# hybrid.net
KiCad netlist of a schematic drawn in EAGLE
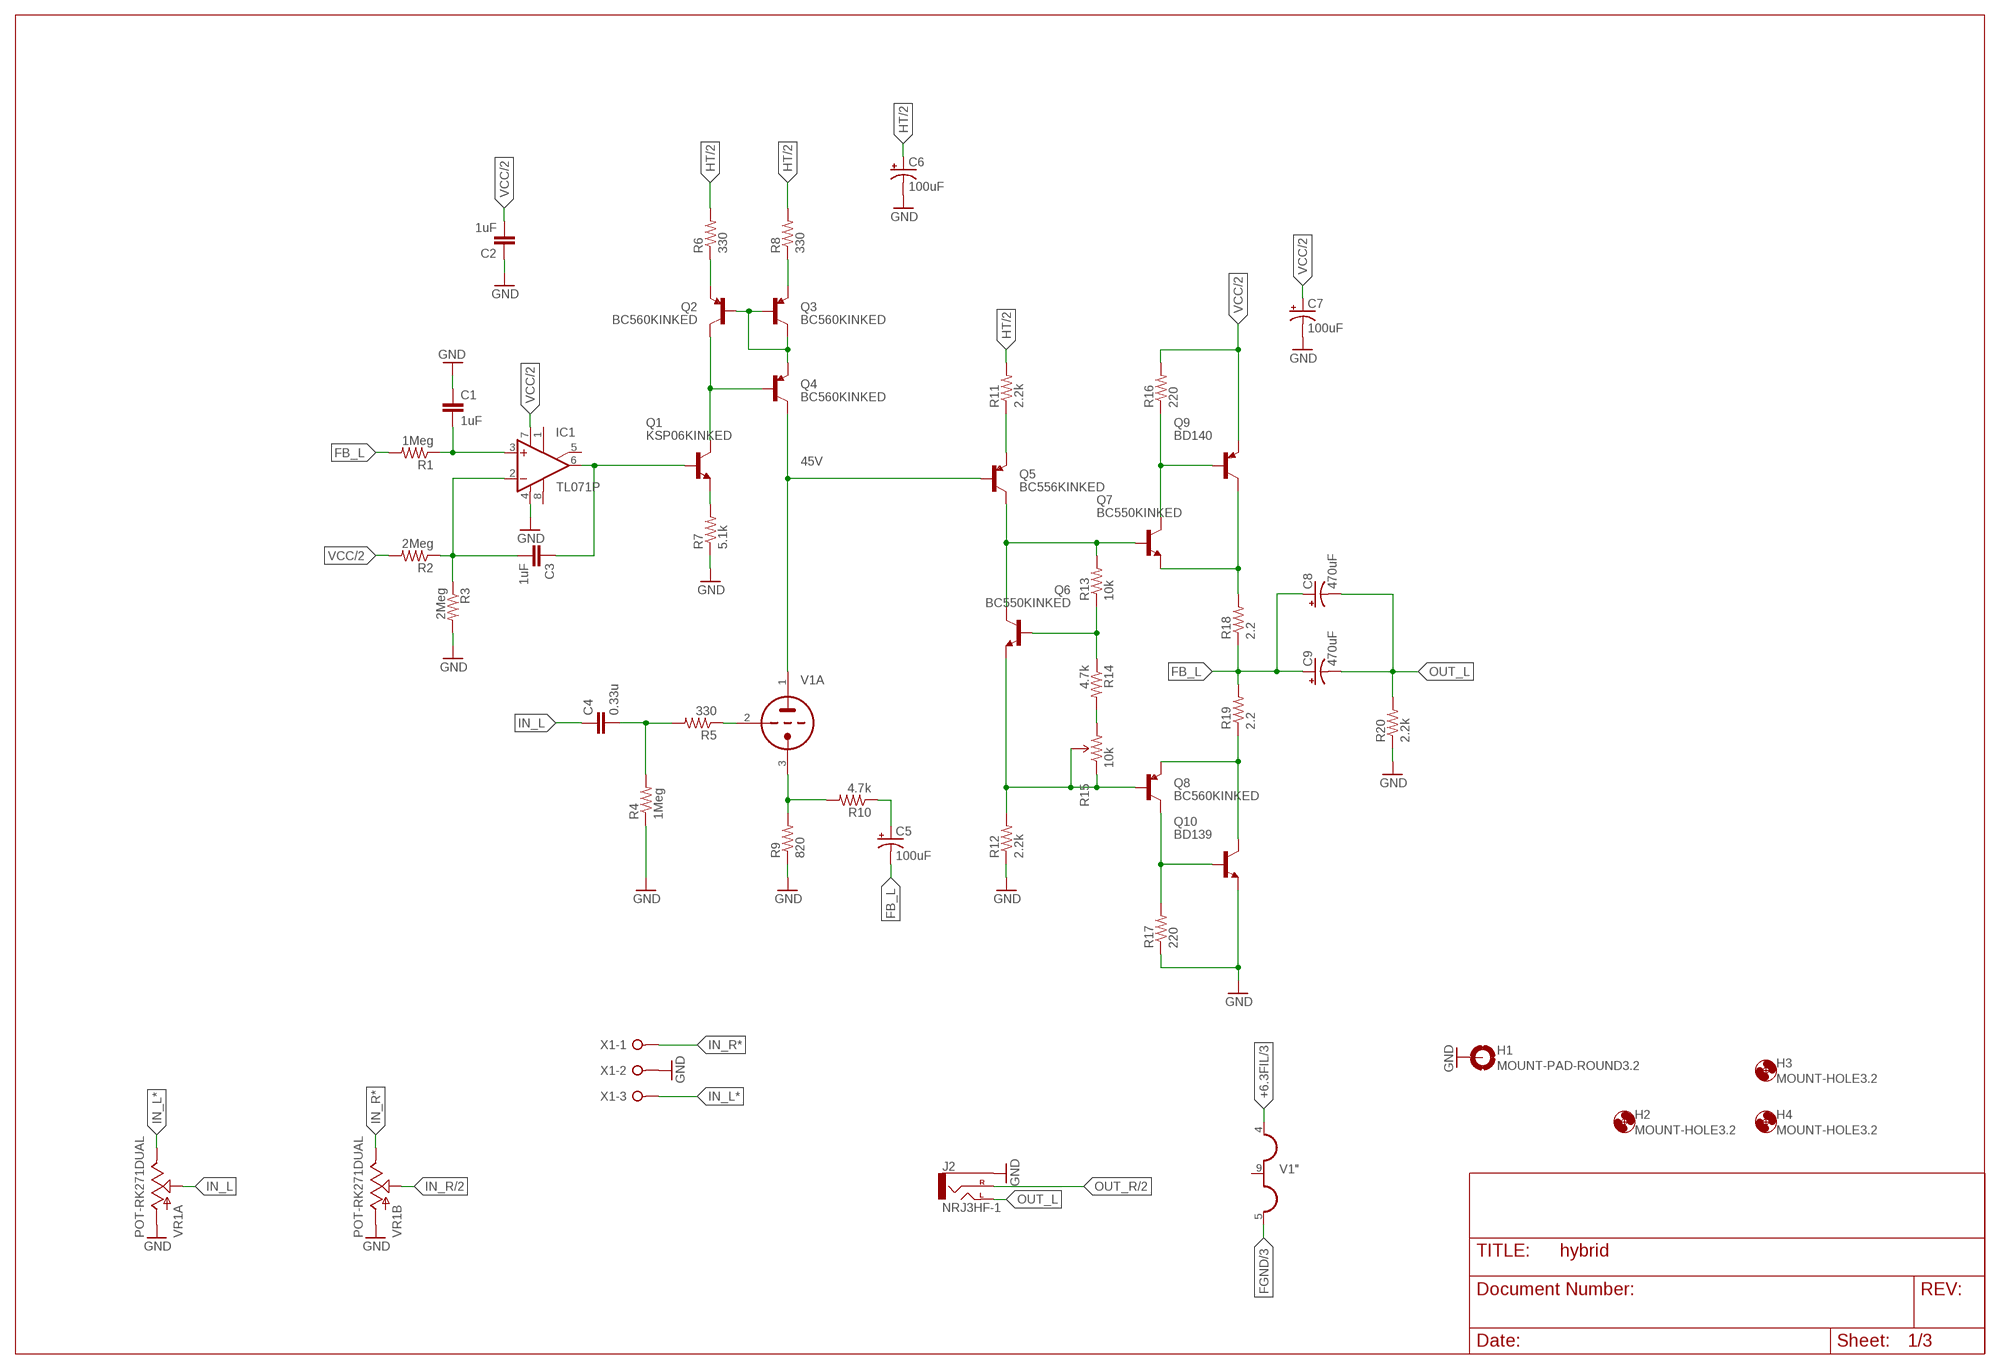
[diagram p0: schematic, sheet 1]
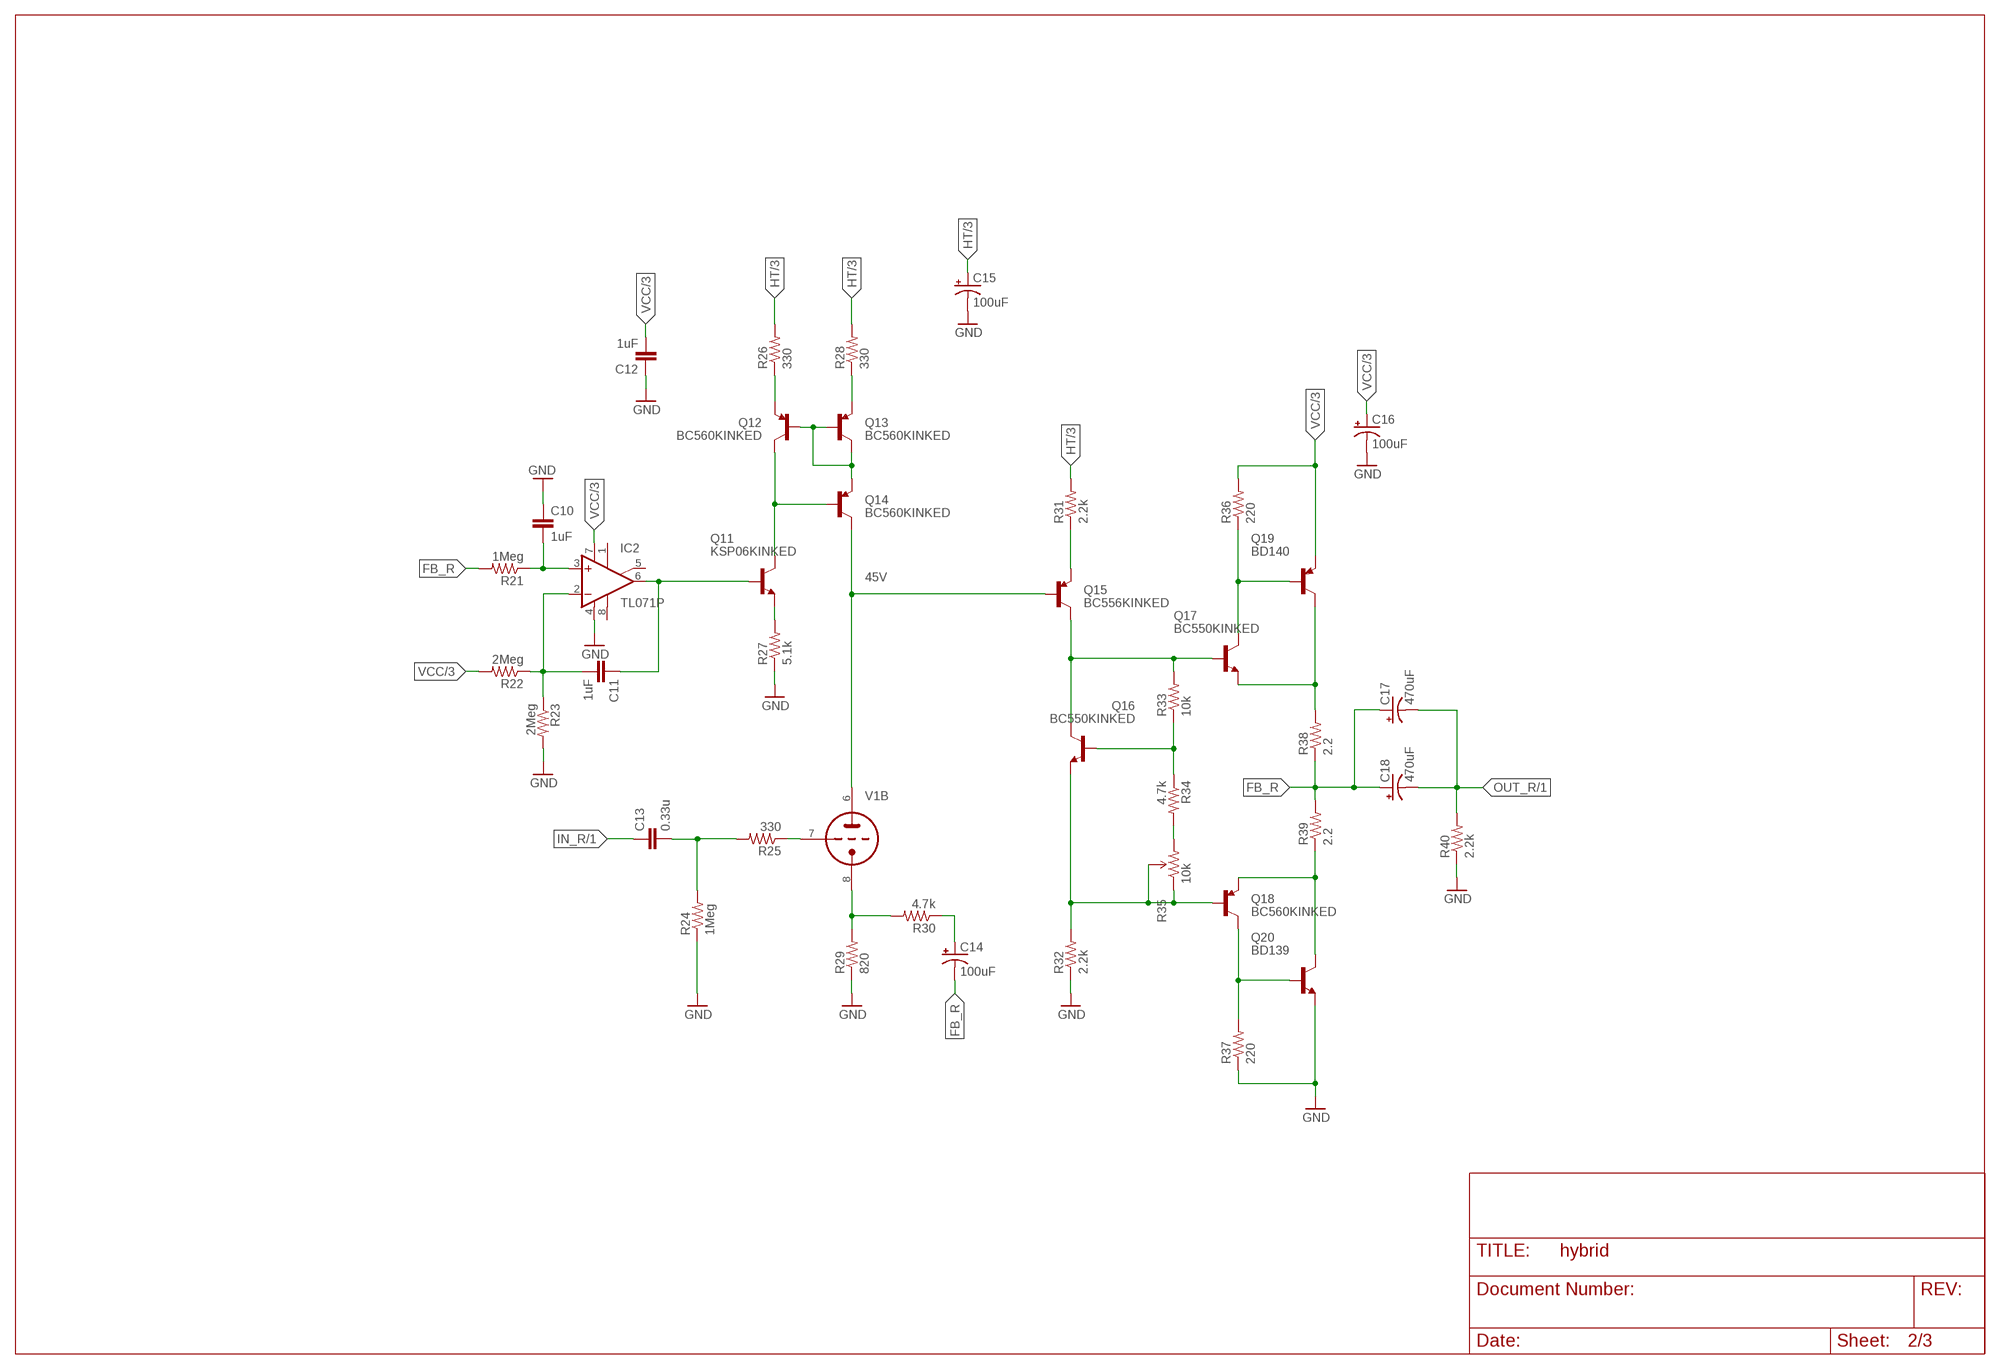
[diagram p1: schematic, sheet 2]
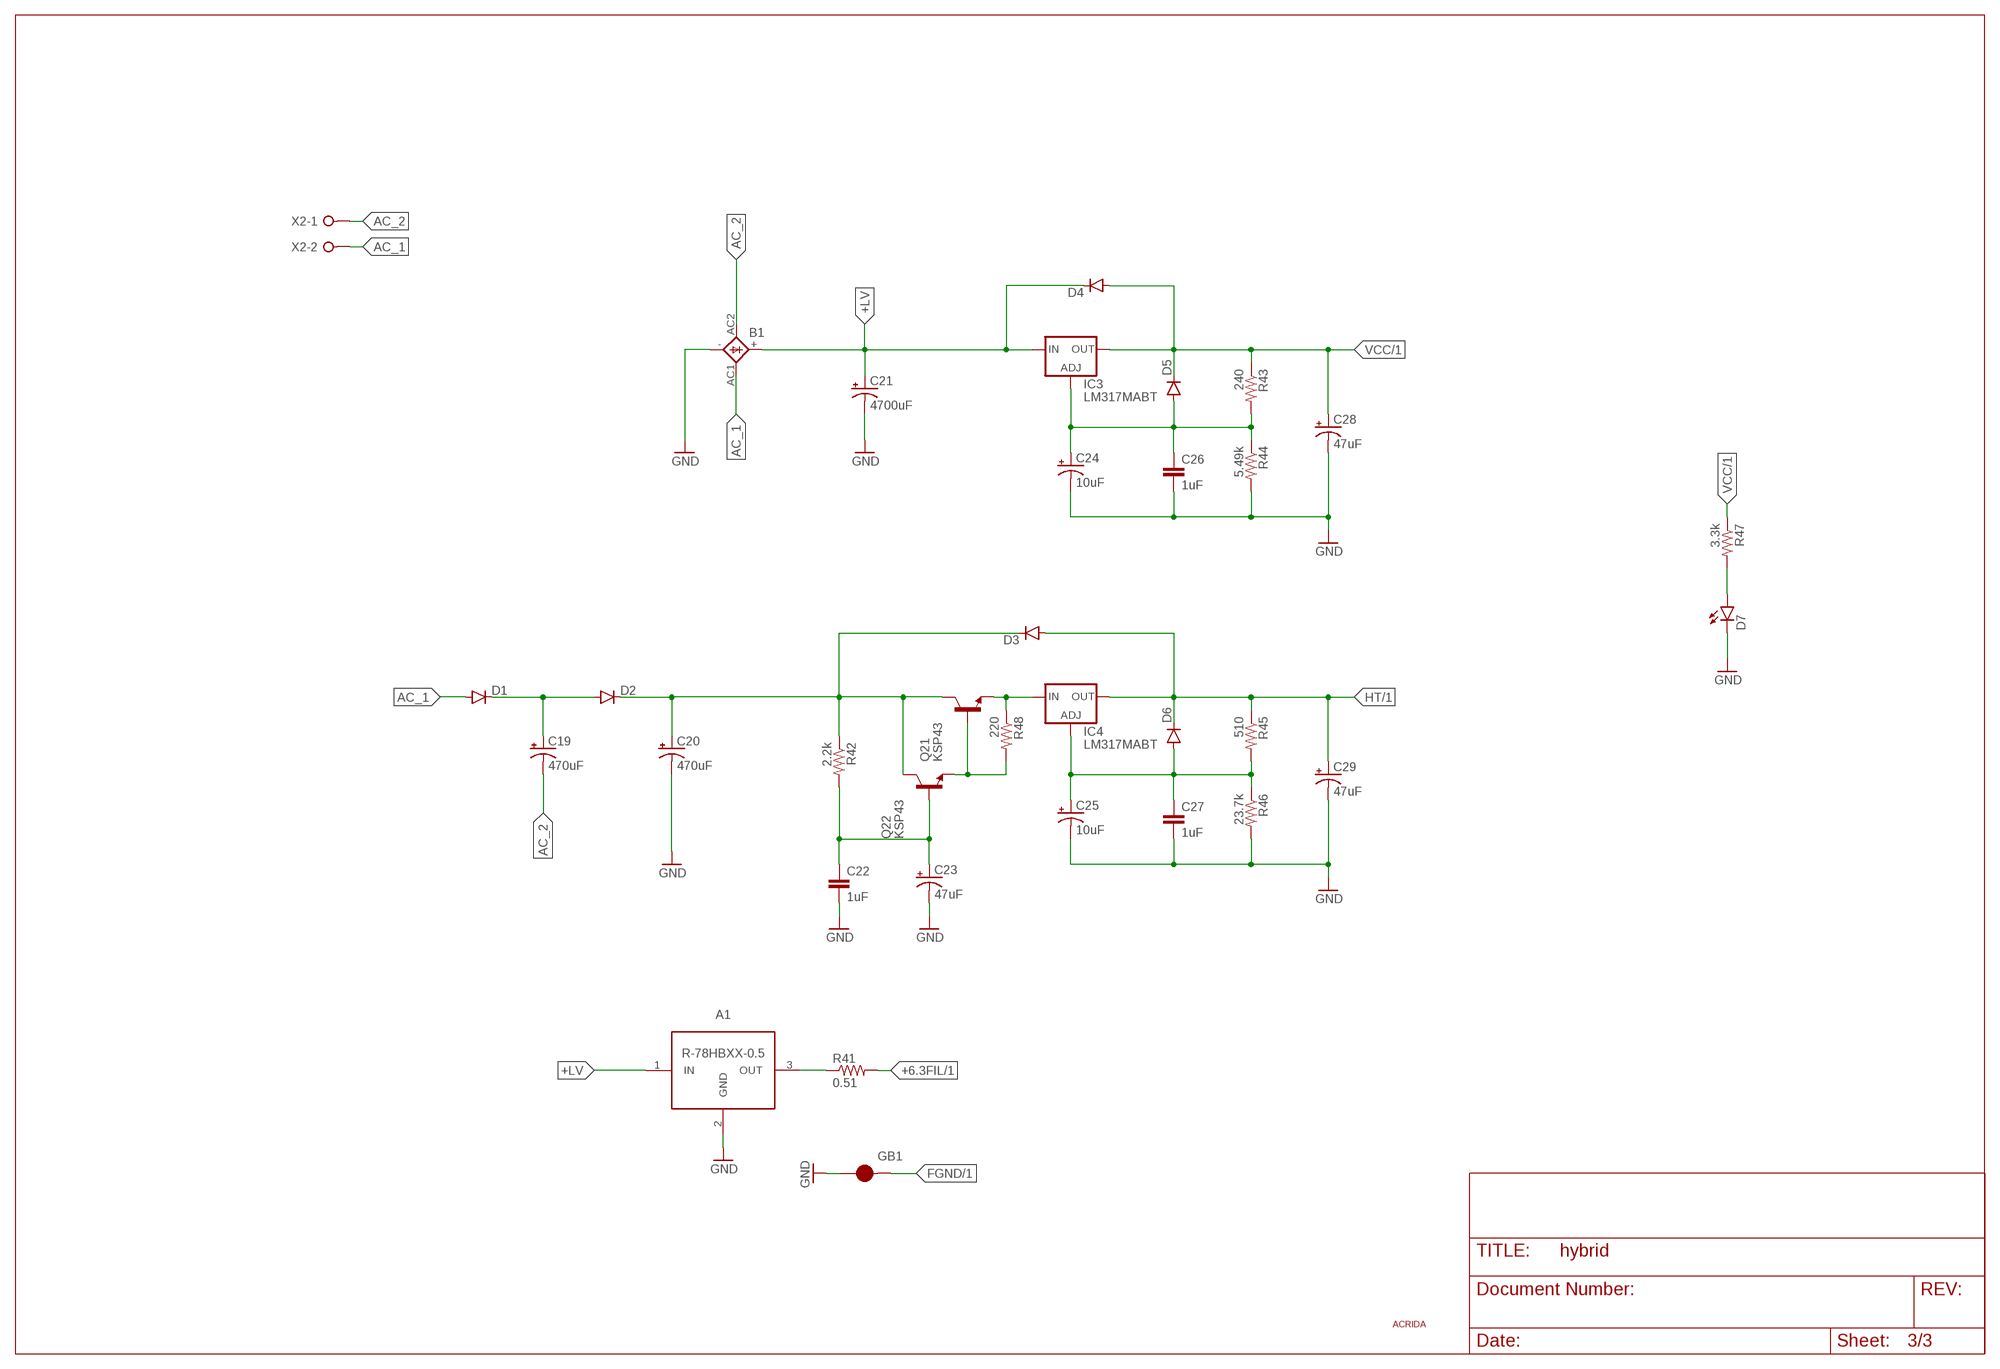
[diagram p2: schematic, sheet 3]

(export (version "E")
  (design (tool "Eeschema 10.0.6"))
  (components
    (comp (ref "C10")
      (value "1uF")
      (footprint "eagle-import:C5B5")
      (libsource (lib "eagle-import") (part "C5/5"))
    )
    (comp (ref "C11")
      (value "1uF")
      (footprint "eagle-import:C5B5")
      (libsource (lib "eagle-import") (part "C5/5"))
    )
    (comp (ref "C12")
      (value "1uF")
      (footprint "eagle-import:CAP-PTH-SMALL")
      (libsource (lib "eagle-import") (part "CAPPTH"))
    )
    (comp (ref "C13")
      (value "0.33u")
      (footprint "eagle-import:C5B7.2")
      (libsource (lib "eagle-import") (part "C5/7.2"))
    )
    (comp (ref "C14")
      (value "100uF")
      (footprint "eagle-import:CPOL-RADIAL-8_3.5")
      (libsource (lib "eagle-import") (part "CAP_POLPTH-8/3.5"))
    )
    (comp (ref "C15")
      (value "100uF")
      (footprint "eagle-import:CPOL-RADIAL-12.5_5")
      (libsource (lib "eagle-import") (part "CAP_POLPTH-12.5/5"))
    )
    (comp (ref "C16")
      (value "100uF")
      (footprint "eagle-import:CPOL-RADIAL-12.5_5")
      (libsource (lib "eagle-import") (part "CAP_POLPTH-12.5/5"))
    )
    (comp (ref "C17")
      (value "470uF")
      (footprint "eagle-import:CPOL-RADIAL-12.5_5")
      (libsource (lib "eagle-import") (part "CAP_POLPTH-12.5/5"))
    )
    (comp (ref "C18")
      (value "470uF")
      (footprint "eagle-import:CPOL-RADIAL-12.5_5")
      (libsource (lib "eagle-import") (part "CAP_POLPTH-12.5/5"))
    )
    (comp (ref "IC2")
      (value "TL071P")
      (footprint "eagle-import:DIL08")
      (libsource (lib "eagle-import") (part "TL071P"))
    )
    (comp (ref "Q11")
      (value "KSP06KINKED")
      (footprint "eagle-import:TO92-BENT")
      (libsource (lib "eagle-import") (part "KSP06KINKED"))
    )
    (comp (ref "Q12")
      (value "BC560KINKED")
      (footprint "eagle-import:TO92-BENT")
      (libsource (lib "eagle-import") (part "BC560KINKED"))
    )
    (comp (ref "Q13")
      (value "BC560KINKED")
      (footprint "eagle-import:TO92-BENT")
      (libsource (lib "eagle-import") (part "BC560KINKED"))
    )
    (comp (ref "Q14")
      (value "BC560KINKED")
      (footprint "eagle-import:TO92-BENT")
      (libsource (lib "eagle-import") (part "BC560KINKED"))
    )
    (comp (ref "Q15")
      (value "BC556KINKED")
      (footprint "eagle-import:TO92-BENT")
      (libsource (lib "eagle-import") (part "BC556KINKED"))
    )
    (comp (ref "Q16")
      (value "BC550KINKED")
      (footprint "eagle-import:TO92-BENT")
      (libsource (lib "eagle-import") (part "BC550KINKED"))
    )
    (comp (ref "Q17")
      (value "BC550KINKED")
      (footprint "eagle-import:TO92-BENT")
      (libsource (lib "eagle-import") (part "BC550KINKED"))
    )
    (comp (ref "Q18")
      (value "BC560KINKED")
      (footprint "eagle-import:TO92-BENT")
      (libsource (lib "eagle-import") (part "BC560KINKED"))
    )
    (comp (ref "Q19")
      (value "BD140")
      (footprint "eagle-import:TO126")
      (libsource (lib "eagle-import") (part "BD140"))
    )
    (comp (ref "Q20")
      (value "BD139")
      (footprint "eagle-import:TO126")
      (libsource (lib "eagle-import") (part "BD139"))
    )
    (comp (ref "R21")
      (value "1Meg")
      (footprint "eagle-import:AXIAL-0.4")
      (libsource (lib "eagle-import") (part "RESISTORPTH-1/4W"))
    )
    (comp (ref "R22")
      (value "2Meg")
      (footprint "eagle-import:AXIAL-0.4")
      (libsource (lib "eagle-import") (part "RESISTORPTH-1/4W"))
    )
    (comp (ref "R23")
      (value "2Meg")
      (footprint "eagle-import:AXIAL-0.4")
      (libsource (lib "eagle-import") (part "RESISTORPTH-1/4W"))
    )
    (comp (ref "R24")
      (value "1Meg")
      (footprint "eagle-import:AXIAL-0.4")
      (libsource (lib "eagle-import") (part "RESISTORPTH-1/4W"))
    )
    (comp (ref "R25")
      (value "330")
      (footprint "eagle-import:AXIAL-0.4")
      (libsource (lib "eagle-import") (part "RESISTORPTH-1/4W"))
    )
    (comp (ref "R26")
      (value "330")
      (footprint "eagle-import:AXIAL-0.4")
      (libsource (lib "eagle-import") (part "RESISTORPTH-1/4W"))
    )
    (comp (ref "R27")
      (value "5.1k")
      (footprint "eagle-import:AXIAL-0.4")
      (libsource (lib "eagle-import") (part "RESISTORPTH-1/4W"))
    )
    (comp (ref "R28")
      (value "330")
      (footprint "eagle-import:AXIAL-0.4")
      (libsource (lib "eagle-import") (part "RESISTORPTH-1/4W"))
    )
    (comp (ref "R29")
      (value "820")
      (footprint "eagle-import:AXIAL-0.4")
      (libsource (lib "eagle-import") (part "RESISTORPTH-1/4W"))
    )
    (comp (ref "R30")
      (value "4.7k")
      (footprint "eagle-import:AXIAL-0.4")
      (libsource (lib "eagle-import") (part "RESISTORPTH-1/4W"))
    )
    (comp (ref "R31")
      (value "2.2k")
      (footprint "eagle-import:AXIAL-0.4")
      (libsource (lib "eagle-import") (part "RESISTORPTH-1/4W"))
    )
    (comp (ref "R32")
      (value "2.2k")
      (footprint "eagle-import:AXIAL-0.4")
      (libsource (lib "eagle-import") (part "RESISTORPTH-1/4W"))
    )
    (comp (ref "R33")
      (value "10k")
      (footprint "eagle-import:AXIAL-0.4")
      (libsource (lib "eagle-import") (part "RESISTORPTH-1/4W"))
    )
    (comp (ref "R34")
      (value "4.7k")
      (footprint "eagle-import:AXIAL-0.4")
      (libsource (lib "eagle-import") (part "RESISTORPTH-1/4W"))
    )
    (comp (ref "R35")
      (value "10k")
      (footprint "eagle-import:3362U-2")
      (libsource (lib "eagle-import") (part "TRIMPOT3362U-2"))
    )
    (comp (ref "R36")
      (value "220")
      (footprint "eagle-import:AXIAL-0.4")
      (libsource (lib "eagle-import") (part "RESISTORPTH-1/4W"))
    )
    (comp (ref "R37")
      (value "220")
      (footprint "eagle-import:AXIAL-0.4")
      (libsource (lib "eagle-import") (part "RESISTORPTH-1/4W"))
    )
    (comp (ref "R38")
      (value "2.2")
      (footprint "eagle-import:AXIAL-0.4")
      (libsource (lib "eagle-import") (part "RESISTORPTH-1/4W"))
    )
    (comp (ref "R39")
      (value "2.2")
      (footprint "eagle-import:AXIAL-0.4")
      (libsource (lib "eagle-import") (part "RESISTORPTH-1/4W"))
    )
    (comp (ref "R40")
      (value "2.2k")
      (footprint "eagle-import:AXIAL-0.4")
      (libsource (lib "eagle-import") (part "RESISTORPTH-1/4W"))
    )
    (comp (ref "V1")
      (value "6DJ8-P21MM-BASE")
      (footprint "eagle-import:NOVAL-21MM")
      (libsource (lib "eagle-import") (part "6DJ8-P21MM-BASE"))
    )
    (comp (ref "A1")
      (value "R-78HBXX-0.5")
      (footprint "eagle-import:R-78HB")
      (libsource (lib "eagle-import") (part "R-78HBXX-0.5"))
    )
    (comp (ref "B1")
      (value "GBU4")
      (footprint "eagle-import:GBU4S")
      (libsource (lib "eagle-import") (part "GBU4"))
    )
    (comp (ref "C19")
      (value "470uF")
      (footprint "eagle-import:CPOL-RADIAL-18_7.5")
      (libsource (lib "eagle-import") (part "CAP_POLPTH-18/7.5"))
    )
    (comp (ref "C20")
      (value "470uF")
      (footprint "eagle-import:CPOL-RADIAL-18_7.5")
      (libsource (lib "eagle-import") (part "CAP_POLPTH-18/7.5"))
    )
    (comp (ref "C21")
      (value "4700uF")
      (footprint "eagle-import:CPOL-SNAPIN-30_10")
      (libsource (lib "eagle-import") (part "CAP_POLSNAPIN-30/10"))
    )
    (comp (ref "C22")
      (value "1uF")
      (footprint "eagle-import:CAP-PTH-5MM")
      (libsource (lib "eagle-import") (part "CAPPTH1"))
    )
    (comp (ref "C23")
      (value "47uF")
      (footprint "eagle-import:CPOL-RADIAL-12_5")
      (libsource (lib "eagle-import") (part "CAP_POLPTH-12/5"))
    )
    (comp (ref "C24")
      (value "10uF")
      (footprint "eagle-import:CPOL-RADIAL-5_2.5")
      (libsource (lib "eagle-import") (part "CAP_POLPTH-5/2.5"))
    )
    (comp (ref "C25")
      (value "10uF")
      (footprint "eagle-import:CPOL-RADIAL-6.5_2.5")
      (libsource (lib "eagle-import") (part "CAP_POLPTH-6.5/2.5"))
    )
    (comp (ref "C26")
      (value "1uF")
      (footprint "eagle-import:CAP-PTH-SMALL")
      (libsource (lib "eagle-import") (part "CAPPTH"))
    )
    (comp (ref "C27")
      (value "1uF")
      (footprint "eagle-import:CAP-PTH-SMALL")
      (libsource (lib "eagle-import") (part "CAPPTH"))
    )
    (comp (ref "C28")
      (value "47uF")
      (footprint "eagle-import:CPOL-RADIAL-8_3.5")
      (libsource (lib "eagle-import") (part "CAP_POLPTH-8/3.5"))
    )
    (comp (ref "C29")
      (value "47uF")
      (footprint "eagle-import:CPOL-RADIAL-8_3.5")
      (libsource (lib "eagle-import") (part "CAP_POLPTH-8/3.5"))
    )
    (comp (ref "D1")
      (value "DIODEPTH")
      (footprint "eagle-import:DIODE-1N4001")
      (libsource (lib "eagle-import") (part "DIODEPTH"))
    )
    (comp (ref "D2")
      (value "DIODEPTH")
      (footprint "eagle-import:DIODE-1N4001")
      (libsource (lib "eagle-import") (part "DIODEPTH"))
    )
    (comp (ref "D3")
      (value "DIODEPTH")
      (footprint "eagle-import:DIODE-1N4001")
      (libsource (lib "eagle-import") (part "DIODEPTH"))
    )
    (comp (ref "D4")
      (value "DIODEPTH")
      (footprint "eagle-import:DIODE-1N4001")
      (libsource (lib "eagle-import") (part "DIODEPTH"))
    )
    (comp (ref "D5")
      (value "DIODEPTH")
      (footprint "eagle-import:DIODE-1N4001")
      (libsource (lib "eagle-import") (part "DIODEPTH"))
    )
    (comp (ref "D6")
      (value "DIODEPTH")
      (footprint "eagle-import:DIODE-1N4001")
      (libsource (lib "eagle-import") (part "DIODEPTH"))
    )
    (comp (ref "D7")
      (value "LED3MM")
      (footprint "eagle-import:LED3MM")
      (libsource (lib "eagle-import") (part "LED3MM"))
    )
    (comp (ref "GB1")
      (value "COPPER-BRIDGESM")
      (footprint "eagle-import:COPPER-BRIDGE-SM")
      (libsource (lib "eagle-import") (part "COPPER-BRIDGESM"))
    )
    (comp (ref "IC3")
      (value "LM317MABT")
      (footprint "eagle-import:TO220L1")
      (libsource (lib "eagle-import") (part "LM317?MABT"))
    )
    (comp (ref "IC4")
      (value "LM317MABT")
      (footprint "eagle-import:TO220L1")
      (libsource (lib "eagle-import") (part "LM317?MABT"))
    )
    (comp (ref "LOGO1")
      (value "ACRIDA-LOGO")
      (footprint "eagle-import:ACRIDA-LOGO")
      (libsource (lib "eagle-import") (part "ACRIDA-LOGO"))
    )
    (comp (ref "Q21")
      (value "KSP43")
      (footprint "eagle-import:TO-92")
      (libsource (lib "eagle-import") (part "KSP43"))
    )
    (comp (ref "Q22")
      (value "KSP43")
      (footprint "eagle-import:TO-92")
      (libsource (lib "eagle-import") (part "KSP43"))
    )
    (comp (ref "R41")
      (value "0.51")
      (footprint "eagle-import:AXIAL-0.5")
      (libsource (lib "eagle-import") (part "my-res_RESISTORPTH-1/2W"))
    )
    (comp (ref "R42")
      (value "2.2k")
      (footprint "eagle-import:AXIAL-0.4")
      (libsource (lib "eagle-import") (part "RESISTORPTH-1/4W"))
    )
    (comp (ref "R43")
      (value "240")
      (footprint "eagle-import:AXIAL-0.4")
      (libsource (lib "eagle-import") (part "RESISTORPTH-1/4W"))
    )
    (comp (ref "R44")
      (value "5.49k")
      (footprint "eagle-import:AXIAL-0.4")
      (libsource (lib "eagle-import") (part "RESISTORPTH-1/4W"))
    )
    (comp (ref "R45")
      (value "510")
      (footprint "eagle-import:AXIAL-0.4")
      (libsource (lib "eagle-import") (part "RESISTORPTH-1/4W"))
    )
    (comp (ref "R46")
      (value "23.7k")
      (footprint "eagle-import:AXIAL-0.4")
      (libsource (lib "eagle-import") (part "RESISTORPTH-1/4W"))
    )
    (comp (ref "R47")
      (value "3.3k")
      (footprint "eagle-import:AXIAL-0.4")
      (libsource (lib "eagle-import") (part "RESISTORPTH-1/4W"))
    )
    (comp (ref "R48")
      (value "220")
      (footprint "eagle-import:AXIAL-0.4")
      (libsource (lib "eagle-import") (part "RESISTORPTH-1/4W"))
    )
    (comp (ref "X2")
      (value "W237-2N")
      (footprint "eagle-import:W237-2N")
      (libsource (lib "eagle-import") (part "W237-2N"))
    )
    (comp (ref "C1")
      (value "1uF")
      (footprint "eagle-import:C5B5")
      (libsource (lib "eagle-import") (part "C5/5"))
    )
    (comp (ref "C2")
      (value "1uF")
      (footprint "eagle-import:CAP-PTH-SMALL")
      (libsource (lib "eagle-import") (part "CAPPTH"))
    )
    (comp (ref "C3")
      (value "1uF")
      (footprint "eagle-import:C5B5")
      (libsource (lib "eagle-import") (part "C5/5"))
    )
    (comp (ref "C4")
      (value "0.33u")
      (footprint "eagle-import:C5B7.2")
      (libsource (lib "eagle-import") (part "C5/7.2"))
    )
    (comp (ref "C5")
      (value "100uF")
      (footprint "eagle-import:CPOL-RADIAL-8_3.5")
      (libsource (lib "eagle-import") (part "CAP_POLPTH-8/3.5"))
    )
    (comp (ref "C6")
      (value "100uF")
      (footprint "eagle-import:CPOL-RADIAL-12.5_5")
      (libsource (lib "eagle-import") (part "CAP_POLPTH-12.5/5"))
    )
    (comp (ref "C7")
      (value "100uF")
      (footprint "eagle-import:CPOL-RADIAL-12.5_5")
      (libsource (lib "eagle-import") (part "CAP_POLPTH-12.5/5"))
    )
    (comp (ref "C8")
      (value "470uF")
      (footprint "eagle-import:CPOL-RADIAL-12.5_5")
      (libsource (lib "eagle-import") (part "CAP_POLPTH-12.5/5"))
    )
    (comp (ref "C9")
      (value "470uF")
      (footprint "eagle-import:CPOL-RADIAL-12.5_5")
      (libsource (lib "eagle-import") (part "CAP_POLPTH-12.5/5"))
    )
    (comp (ref "H1")
      (value "MOUNT-PAD-ROUND3.2")
      (footprint "eagle-import:3,2-PAD")
      (libsource (lib "eagle-import") (part "MOUNT-PAD-ROUND3.2"))
    )
    (comp (ref "H2")
      (value "MOUNT-HOLE3.2")
      (footprint "eagle-import:3,2")
      (libsource (lib "eagle-import") (part "MOUNT-HOLE3.2"))
    )
    (comp (ref "H3")
      (value "MOUNT-HOLE3.2")
      (footprint "eagle-import:3,2")
      (libsource (lib "eagle-import") (part "MOUNT-HOLE3.2"))
    )
    (comp (ref "H4")
      (value "MOUNT-HOLE3.2")
      (footprint "eagle-import:3,2")
      (libsource (lib "eagle-import") (part "MOUNT-HOLE3.2"))
    )
    (comp (ref "IC1")
      (value "TL071P")
      (footprint "eagle-import:DIL08")
      (libsource (lib "eagle-import") (part "TL071P"))
    )
    (comp (ref "J2")
      (value "NRJ3HF-1")
      (footprint "eagle-import:NRJ3HF")
      (libsource (lib "eagle-import") (part "NRJ3HF-1"))
    )
    (comp (ref "Q1")
      (value "KSP06KINKED")
      (footprint "eagle-import:TO92-BENT")
      (libsource (lib "eagle-import") (part "KSP06KINKED"))
    )
    (comp (ref "Q2")
      (value "BC560KINKED")
      (footprint "eagle-import:TO92-BENT")
      (libsource (lib "eagle-import") (part "BC560KINKED"))
    )
    (comp (ref "Q3")
      (value "BC560KINKED")
      (footprint "eagle-import:TO92-BENT")
      (libsource (lib "eagle-import") (part "BC560KINKED"))
    )
    (comp (ref "Q4")
      (value "BC560KINKED")
      (footprint "eagle-import:TO92-BENT")
      (libsource (lib "eagle-import") (part "BC560KINKED"))
    )
    (comp (ref "Q5")
      (value "BC556KINKED")
      (footprint "eagle-import:TO92-BENT")
      (libsource (lib "eagle-import") (part "BC556KINKED"))
    )
    (comp (ref "Q6")
      (value "BC550KINKED")
      (footprint "eagle-import:TO92-BENT")
      (libsource (lib "eagle-import") (part "BC550KINKED"))
    )
    (comp (ref "Q7")
      (value "BC550KINKED")
      (footprint "eagle-import:TO92-BENT")
      (libsource (lib "eagle-import") (part "BC550KINKED"))
    )
    (comp (ref "Q8")
      (value "BC560KINKED")
      (footprint "eagle-import:TO92-BENT")
      (libsource (lib "eagle-import") (part "BC560KINKED"))
    )
    (comp (ref "Q9")
      (value "BD140")
      (footprint "eagle-import:TO126")
      (libsource (lib "eagle-import") (part "BD140"))
    )
    (comp (ref "Q10")
      (value "BD139")
      (footprint "eagle-import:TO126")
      (libsource (lib "eagle-import") (part "BD139"))
    )
    (comp (ref "R1")
      (value "1Meg")
      (footprint "eagle-import:AXIAL-0.4")
      (libsource (lib "eagle-import") (part "RESISTORPTH-1/4W"))
    )
    (comp (ref "R2")
      (value "2Meg")
      (footprint "eagle-import:AXIAL-0.4")
      (libsource (lib "eagle-import") (part "RESISTORPTH-1/4W"))
    )
    (comp (ref "R3")
      (value "2Meg")
      (footprint "eagle-import:AXIAL-0.4")
      (libsource (lib "eagle-import") (part "RESISTORPTH-1/4W"))
    )
    (comp (ref "R4")
      (value "1Meg")
      (footprint "eagle-import:AXIAL-0.4")
      (libsource (lib "eagle-import") (part "RESISTORPTH-1/4W"))
    )
    (comp (ref "R5")
      (value "330")
      (footprint "eagle-import:AXIAL-0.4")
      (libsource (lib "eagle-import") (part "RESISTORPTH-1/4W"))
    )
    (comp (ref "R6")
      (value "330")
      (footprint "eagle-import:AXIAL-0.4")
      (libsource (lib "eagle-import") (part "RESISTORPTH-1/4W"))
    )
    (comp (ref "R7")
      (value "5.1k")
      (footprint "eagle-import:AXIAL-0.4")
      (libsource (lib "eagle-import") (part "RESISTORPTH-1/4W"))
    )
    (comp (ref "R8")
      (value "330")
      (footprint "eagle-import:AXIAL-0.4")
      (libsource (lib "eagle-import") (part "RESISTORPTH-1/4W"))
    )
    (comp (ref "R9")
      (value "820")
      (footprint "eagle-import:AXIAL-0.4")
      (libsource (lib "eagle-import") (part "RESISTORPTH-1/4W"))
    )
    (comp (ref "R10")
      (value "4.7k")
      (footprint "eagle-import:AXIAL-0.4")
      (libsource (lib "eagle-import") (part "RESISTORPTH-1/4W"))
    )
    (comp (ref "R11")
      (value "2.2k")
      (footprint "eagle-import:AXIAL-0.4")
      (libsource (lib "eagle-import") (part "RESISTORPTH-1/4W"))
    )
    (comp (ref "R12")
      (value "2.2k")
      (footprint "eagle-import:AXIAL-0.4")
      (libsource (lib "eagle-import") (part "RESISTORPTH-1/4W"))
    )
    (comp (ref "R13")
      (value "10k")
      (footprint "eagle-import:AXIAL-0.4")
      (libsource (lib "eagle-import") (part "RESISTORPTH-1/4W"))
    )
    (comp (ref "R14")
      (value "4.7k")
      (footprint "eagle-import:AXIAL-0.4")
      (libsource (lib "eagle-import") (part "RESISTORPTH-1/4W"))
    )
    (comp (ref "R15")
      (value "10k")
      (footprint "eagle-import:3362U-2")
      (libsource (lib "eagle-import") (part "TRIMPOT3362U-2"))
    )
    (comp (ref "R16")
      (value "220")
      (footprint "eagle-import:AXIAL-0.4")
      (libsource (lib "eagle-import") (part "RESISTORPTH-1/4W"))
    )
    (comp (ref "R17")
      (value "220")
      (footprint "eagle-import:AXIAL-0.4")
      (libsource (lib "eagle-import") (part "RESISTORPTH-1/4W"))
    )
    (comp (ref "R18")
      (value "2.2")
      (footprint "eagle-import:AXIAL-0.4")
      (libsource (lib "eagle-import") (part "RESISTORPTH-1/4W"))
    )
    (comp (ref "R19")
      (value "2.2")
      (footprint "eagle-import:AXIAL-0.4")
      (libsource (lib "eagle-import") (part "RESISTORPTH-1/4W"))
    )
    (comp (ref "R20")
      (value "2.2k")
      (footprint "eagle-import:AXIAL-0.4")
      (libsource (lib "eagle-import") (part "RESISTORPTH-1/4W"))
    )
    (comp (ref "VR1")
      (value "POT-RK271DUAL")
      (footprint "eagle-import:RK271+PTD902")
      (libsource (lib "eagle-import") (part "POT-RK271DUAL"))
    )
    (comp (ref "X1")
      (value "W237-3E")
      (footprint "eagle-import:W237-3E")
      (libsource (lib "eagle-import") (part "W237-3E"))
    )
  )
  (nets
    (net (code "1") (name "+6.3FIL") (class "Default")
      (node (ref "R41") (pin "P$2") (pinfunction "2_P$2") (pintype "passive"))
      (node (ref "V1") (pin "4") (pinfunction "H1_4") (pintype "passive"))
    )
    (net (code "2") (name "+LV") (class "Default")
      (node (ref "A1") (pin "1") (pinfunction "IN_1") (pintype "bidirectional"))
      (node (ref "B1") (pin "+") (pinfunction "+_+") (pintype "passive"))
      (node (ref "C21") (pin "1") (pinfunction "+_1") (pintype "passive"))
      (node (ref "D4") (pin "C") (pinfunction "C_C") (pintype "passive"))
      (node (ref "IC3") (pin "3") (pinfunction "IN_3") (pintype "input"))
    )
    (net (code "3") (name "AC_1") (class "Default")
      (node (ref "B1") (pin "AC1") (pinfunction "AC2_AC1") (pintype "passive"))
      (node (ref "D1") (pin "A") (pinfunction "A_A") (pintype "passive"))
      (node (ref "X2") (pin "2") (pinfunction "KL_2") (pintype "passive"))
    )
    (net (code "4") (name "AC_2") (class "Default")
      (node (ref "B1") (pin "AC2") (pinfunction "AC1_AC2") (pintype "passive"))
      (node (ref "C19") (pin "2") (pinfunction "-_2") (pintype "passive"))
      (node (ref "X2") (pin "1") (pinfunction "KL_1") (pintype "passive"))
    )
    (net (code "5") (name "FB_L") (class "Default")
      (node (ref "C5") (pin "2") (pinfunction "-_2") (pintype "passive"))
      (node (ref "C8") (pin "+") (pinfunction "+_+") (pintype "passive"))
      (node (ref "C9") (pin "+") (pinfunction "+_+") (pintype "passive"))
      (node (ref "R1") (pin "P$2") (pinfunction "2_P$2") (pintype "passive"))
      (node (ref "R18") (pin "P$1") (pinfunction "1_P$1") (pintype "passive"))
      (node (ref "R19") (pin "P$2") (pinfunction "2_P$2") (pintype "passive"))
    )
    (net (code "6") (name "FB_R") (class "Default")
      (node (ref "C14") (pin "2") (pinfunction "-_2") (pintype "passive"))
      (node (ref "C17") (pin "+") (pinfunction "+_+") (pintype "passive"))
      (node (ref "C18") (pin "+") (pinfunction "+_+") (pintype "passive"))
      (node (ref "R21") (pin "P$2") (pinfunction "2_P$2") (pintype "passive"))
      (node (ref "R38") (pin "P$1") (pinfunction "1_P$1") (pintype "passive"))
      (node (ref "R39") (pin "P$2") (pinfunction "2_P$2") (pintype "passive"))
    )
    (net (code "7") (name "FGND") (class "Default")
      (node (ref "GB1") (pin "2") (pinfunction "2_2") (pintype "passive"))
      (node (ref "V1") (pin "5") (pinfunction "H3_5") (pintype "passive"))
    )
    (net (code "8") (name "GND") (class "Default")
      (node (ref "A1") (pin "2") (pinfunction "GND_2") (pintype "bidirectional"))
      (node (ref "B1") (pin "-") (pinfunction "-_-") (pintype "passive"))
      (node (ref "C1") (pin "1") (pinfunction "1_1") (pintype "passive"))
      (node (ref "C10") (pin "1") (pinfunction "1_1") (pintype "passive"))
      (node (ref "C12") (pin "1") (pinfunction "1_1") (pintype "passive"))
      (node (ref "C15") (pin "-") (pinfunction "-_-") (pintype "passive"))
      (node (ref "C16") (pin "-") (pinfunction "-_-") (pintype "passive"))
      (node (ref "C2") (pin "1") (pinfunction "1_1") (pintype "passive"))
      (node (ref "C20") (pin "2") (pinfunction "-_2") (pintype "passive"))
      (node (ref "C21") (pin "2") (pinfunction "-_2") (pintype "passive"))
      (node (ref "C22") (pin "2") (pinfunction "2_2") (pintype "passive"))
      (node (ref "C23") (pin "-") (pinfunction "-_-") (pintype "passive"))
      (node (ref "C24") (pin "2") (pinfunction "-_2") (pintype "passive"))
      (node (ref "C25") (pin "2") (pinfunction "-_2") (pintype "passive"))
      (node (ref "C26") (pin "2") (pinfunction "2_2") (pintype "passive"))
      (node (ref "C27") (pin "2") (pinfunction "2_2") (pintype "passive"))
      (node (ref "C28") (pin "2") (pinfunction "-_2") (pintype "passive"))
      (node (ref "C29") (pin "2") (pinfunction "-_2") (pintype "passive"))
      (node (ref "C6") (pin "-") (pinfunction "-_-") (pintype "passive"))
      (node (ref "C7") (pin "-") (pinfunction "-_-") (pintype "passive"))
      (node (ref "D7") (pin "K") (pinfunction "C_K") (pintype "passive"))
      (node (ref "GB1") (pin "1") (pinfunction "1_1") (pintype "passive"))
      (node (ref "H1") (pin "B3,2") (pinfunction "MOUNT_B3,2") (pintype "passive"))
      (node (ref "IC1") (pin "4") (pinfunction "V-_4") (pintype "power_in"))
      (node (ref "IC2") (pin "4") (pinfunction "V-_4") (pintype "power_in"))
      (node (ref "J2") (pin "S") (pinfunction "SLEEVE_S") (pintype "bidirectional"))
      (node (ref "Q10") (pin "1") (pinfunction "E_1") (pintype "passive"))
      (node (ref "Q20") (pin "1") (pinfunction "E_1") (pintype "passive"))
      (node (ref "R12") (pin "P$1") (pinfunction "1_P$1") (pintype "passive"))
      (node (ref "R17") (pin "P$1") (pinfunction "1_P$1") (pintype "passive"))
      (node (ref "R20") (pin "P$1") (pinfunction "1_P$1") (pintype "passive"))
      (node (ref "R23") (pin "P$2") (pinfunction "2_P$2") (pintype "passive"))
      (node (ref "R24") (pin "P$1") (pinfunction "1_P$1") (pintype "passive"))
      (node (ref "R27") (pin "P$1") (pinfunction "1_P$1") (pintype "passive"))
      (node (ref "R29") (pin "P$1") (pinfunction "1_P$1") (pintype "passive"))
      (node (ref "R3") (pin "P$2") (pinfunction "2_P$2") (pintype "passive"))
      (node (ref "R32") (pin "P$1") (pinfunction "1_P$1") (pintype "passive"))
      (node (ref "R37") (pin "P$1") (pinfunction "1_P$1") (pintype "passive"))
      (node (ref "R4") (pin "P$1") (pinfunction "1_P$1") (pintype "passive"))
      (node (ref "R40") (pin "P$1") (pinfunction "1_P$1") (pintype "passive"))
      (node (ref "R44") (pin "P$2") (pinfunction "2_P$2") (pintype "passive"))
      (node (ref "R46") (pin "P$2") (pinfunction "2_P$2") (pintype "passive"))
      (node (ref "R7") (pin "P$1") (pinfunction "1_P$1") (pintype "passive"))
      (node (ref "R9") (pin "P$1") (pinfunction "1_P$1") (pintype "passive"))
      (node (ref "VR1") (pin "1.1.1") (pinfunction "A_1.1.1") (pintype "passive"))
      (node (ref "VR1") (pin "1.1.2") (pinfunction "A_1.1.2") (pintype "passive"))
      (node (ref "VR1") (pin "2.1.1") (pinfunction "A_2.1.1") (pintype "passive"))
      (node (ref "VR1") (pin "2.1.2") (pinfunction "A_2.1.2") (pintype "passive"))
      (node (ref "X1") (pin "2") (pinfunction "KL_2") (pintype "passive"))
    )
    (net (code "9") (name "HT") (class "Default")
      (node (ref "C15") (pin "+") (pinfunction "+_+") (pintype "passive"))
      (node (ref "C29") (pin "1") (pinfunction "+_1") (pintype "passive"))
      (node (ref "C6") (pin "+") (pinfunction "+_+") (pintype "passive"))
      (node (ref "D3") (pin "A") (pinfunction "A_A") (pintype "passive"))
      (node (ref "D6") (pin "C") (pinfunction "C_C") (pintype "passive"))
      (node (ref "IC4") (pin "2") (pinfunction "OUT_2") (pintype "passive"))
      (node (ref "R11") (pin "P$2") (pinfunction "2_P$2") (pintype "passive"))
      (node (ref "R26") (pin "P$2") (pinfunction "2_P$2") (pintype "passive"))
      (node (ref "R28") (pin "P$2") (pinfunction "2_P$2") (pintype "passive"))
      (node (ref "R31") (pin "P$2") (pinfunction "2_P$2") (pintype "passive"))
      (node (ref "R45") (pin "P$1") (pinfunction "1_P$1") (pintype "passive"))
      (node (ref "R6") (pin "P$2") (pinfunction "2_P$2") (pintype "passive"))
      (node (ref "R8") (pin "P$2") (pinfunction "2_P$2") (pintype "passive"))
    )
    (net (code "10") (name "IN_L") (class "Default")
      (node (ref "C4") (pin "1") (pinfunction "1_1") (pintype "passive"))
      (node (ref "VR1") (pin "1.2") (pinfunction "S_1.2") (pintype "passive"))
    )
    (net (code "11") (name "IN_L*") (class "Default")
      (node (ref "VR1") (pin "1.3.1") (pinfunction "E_1.3.1") (pintype "passive"))
      (node (ref "VR1") (pin "1.3.2") (pinfunction "E_1.3.2") (pintype "passive"))
      (node (ref "X1") (pin "3") (pinfunction "KL_3") (pintype "passive"))
    )
    (net (code "12") (name "IN_R") (class "Default")
      (node (ref "C13") (pin "1") (pinfunction "1_1") (pintype "passive"))
      (node (ref "VR1") (pin "2.2.1") (pinfunction "S_2.2.1") (pintype "passive"))
      (node (ref "VR1") (pin "2.2.2") (pinfunction "S_2.2.2") (pintype "passive"))
    )
    (net (code "13") (name "IN_R*") (class "Default")
      (node (ref "VR1") (pin "2.3.1") (pinfunction "E_2.3.1") (pintype "passive"))
      (node (ref "VR1") (pin "2.3.2") (pinfunction "E_2.3.2") (pintype "passive"))
      (node (ref "X1") (pin "1") (pinfunction "KL_1") (pintype "passive"))
    )
    (net (code "14") (name "Net-(A1-OUT)") (class "Default")
      (node (ref "A1") (pin "3") (pinfunction "OUT_3") (pintype "bidirectional"))
      (node (ref "R41") (pin "P$1") (pinfunction "1_P$1") (pintype "passive"))
    )
    (net (code "15") (name "Net-(C5-+)") (class "Default")
      (node (ref "C5") (pin "1") (pinfunction "+_1") (pintype "passive"))
      (node (ref "R10") (pin "P$1") (pinfunction "1_P$1") (pintype "passive"))
    )
    (net (code "16") (name "Net-(C14-+)") (class "Default")
      (node (ref "C14") (pin "1") (pinfunction "+_1") (pintype "passive"))
      (node (ref "R30") (pin "P$1") (pinfunction "1_P$1") (pintype "passive"))
    )
    (net (code "17") (name "Net-(C19-+)") (class "Default")
      (node (ref "C19") (pin "1") (pinfunction "+_1") (pintype "passive"))
      (node (ref "D1") (pin "C") (pinfunction "C_C") (pintype "passive"))
      (node (ref "D2") (pin "A") (pinfunction "A_A") (pintype "passive"))
    )
    (net (code "18") (name "Net-(C20-+)") (class "Default")
      (node (ref "C20") (pin "1") (pinfunction "+_1") (pintype "passive"))
      (node (ref "D2") (pin "C") (pinfunction "C_C") (pintype "passive"))
      (node (ref "D3") (pin "C") (pinfunction "C_C") (pintype "passive"))
      (node (ref "Q21") (pin "3") (pinfunction "C_3") (pintype "passive"))
      (node (ref "Q22") (pin "3") (pinfunction "C_3") (pintype "passive"))
      (node (ref "R42") (pin "P$1") (pinfunction "1_P$1") (pintype "passive"))
    )
    (net (code "19") (name "Net-(C24-+)") (class "Default")
      (node (ref "C24") (pin "1") (pinfunction "+_1") (pintype "passive"))
      (node (ref "C26") (pin "1") (pinfunction "1_1") (pintype "passive"))
      (node (ref "D5") (pin "A") (pinfunction "A_A") (pintype "passive"))
      (node (ref "IC3") (pin "1") (pinfunction "ADJ_1") (pintype "input"))
      (node (ref "R43") (pin "P$2") (pinfunction "2_P$2") (pintype "passive"))
      (node (ref "R44") (pin "P$1") (pinfunction "1_P$1") (pintype "passive"))
    )
    (net (code "20") (name "Net-(C25-+)") (class "Default")
      (node (ref "C25") (pin "1") (pinfunction "+_1") (pintype "passive"))
      (node (ref "C27") (pin "1") (pinfunction "1_1") (pintype "passive"))
      (node (ref "D6") (pin "A") (pinfunction "A_A") (pintype "passive"))
      (node (ref "IC4") (pin "1") (pinfunction "ADJ_1") (pintype "input"))
      (node (ref "R45") (pin "P$2") (pinfunction "2_P$2") (pintype "passive"))
      (node (ref "R46") (pin "P$1") (pinfunction "1_P$1") (pintype "passive"))
    )
    (net (code "21") (name "Net-(IC1-+IN)") (class "Default")
      (node (ref "C1") (pin "2") (pinfunction "2_2") (pintype "passive"))
      (node (ref "IC1") (pin "3") (pinfunction "+IN_3") (pintype "input"))
      (node (ref "R1") (pin "P$1") (pinfunction "1_P$1") (pintype "passive"))
    )
    (net (code "22") (name "Net-(IC1--IN)") (class "Default")
      (node (ref "C3") (pin "2") (pinfunction "2_2") (pintype "passive"))
      (node (ref "IC1") (pin "2") (pinfunction "-IN_2") (pintype "input"))
      (node (ref "R2") (pin "P$1") (pinfunction "1_P$1") (pintype "passive"))
      (node (ref "R3") (pin "P$1") (pinfunction "1_P$1") (pintype "passive"))
    )
    (net (code "23") (name "Net-(IC1-OUT)") (class "Default")
      (node (ref "C3") (pin "1") (pinfunction "1_1") (pintype "passive"))
      (node (ref "IC1") (pin "6") (pinfunction "OUT_6") (pintype "output"))
      (node (ref "Q1") (pin "2") (pinfunction "B_2") (pintype "passive"))
    )
    (net (code "24") (name "Net-(IC2-+IN)") (class "Default")
      (node (ref "C10") (pin "2") (pinfunction "2_2") (pintype "passive"))
      (node (ref "IC2") (pin "3") (pinfunction "+IN_3") (pintype "input"))
      (node (ref "R21") (pin "P$1") (pinfunction "1_P$1") (pintype "passive"))
    )
    (net (code "25") (name "Net-(IC2--IN)") (class "Default")
      (node (ref "C11") (pin "2") (pinfunction "2_2") (pintype "passive"))
      (node (ref "IC2") (pin "2") (pinfunction "-IN_2") (pintype "input"))
      (node (ref "R22") (pin "P$1") (pinfunction "1_P$1") (pintype "passive"))
      (node (ref "R23") (pin "P$1") (pinfunction "1_P$1") (pintype "passive"))
    )
    (net (code "26") (name "Net-(IC2-OUT)") (class "Default")
      (node (ref "C11") (pin "1") (pinfunction "1_1") (pintype "passive"))
      (node (ref "IC2") (pin "6") (pinfunction "OUT_6") (pintype "output"))
      (node (ref "Q11") (pin "2") (pinfunction "B_2") (pintype "passive"))
    )
    (net (code "27") (name "Net-(IC4-IN)") (class "Default")
      (node (ref "IC4") (pin "3") (pinfunction "IN_3") (pintype "input"))
      (node (ref "Q21") (pin "1") (pinfunction "E_1") (pintype "passive"))
      (node (ref "R48") (pin "P$1") (pinfunction "1_P$1") (pintype "passive"))
    )
    (net (code "28") (name "Net-(Q1-C)") (class "Default")
      (node (ref "Q1") (pin "3") (pinfunction "C_3") (pintype "passive"))
      (node (ref "Q2") (pin "1") (pinfunction "C_1") (pintype "passive"))
      (node (ref "Q4") (pin "2") (pinfunction "B_2") (pintype "passive"))
    )
    (net (code "29") (name "Net-(Q1-E)") (class "Default")
      (node (ref "Q1") (pin "1") (pinfunction "E_1") (pintype "passive"))
      (node (ref "R7") (pin "P$2") (pinfunction "2_P$2") (pintype "passive"))
    )
    (net (code "30") (name "Net-(Q2-B)") (class "Default")
      (node (ref "Q2") (pin "2") (pinfunction "B_2") (pintype "passive"))
      (node (ref "Q3") (pin "1") (pinfunction "C_1") (pintype "passive"))
      (node (ref "Q3") (pin "2") (pinfunction "B_2") (pintype "passive"))
      (node (ref "Q4") (pin "3") (pinfunction "E_3") (pintype "passive"))
    )
    (net (code "31") (name "Net-(Q2-E)") (class "Default")
      (node (ref "Q2") (pin "3") (pinfunction "E_3") (pintype "passive"))
      (node (ref "R6") (pin "P$1") (pinfunction "1_P$1") (pintype "passive"))
    )
    (net (code "32") (name "Net-(Q3-E)") (class "Default")
      (node (ref "Q3") (pin "3") (pinfunction "E_3") (pintype "passive"))
      (node (ref "R8") (pin "P$1") (pinfunction "1_P$1") (pintype "passive"))
    )
    (net (code "33") (name "Net-(Q4-C)") (class "Default")
      (node (ref "Q4") (pin "1") (pinfunction "C_1") (pintype "passive"))
      (node (ref "Q5") (pin "2") (pinfunction "B_2") (pintype "passive"))
      (node (ref "V1") (pin "1") (pinfunction "TA_1") (pintype "passive"))
    )
    (net (code "34") (name "Net-(Q5-C)") (class "Default")
      (node (ref "Q5") (pin "1") (pinfunction "C_1") (pintype "passive"))
      (node (ref "Q6") (pin "1") (pinfunction "C_1") (pintype "passive"))
      (node (ref "Q7") (pin "2") (pinfunction "B_2") (pintype "passive"))
      (node (ref "R13") (pin "P$2") (pinfunction "2_P$2") (pintype "passive"))
    )
    (net (code "35") (name "Net-(Q5-E)") (class "Default")
      (node (ref "Q5") (pin "3") (pinfunction "E_3") (pintype "passive"))
      (node (ref "R11") (pin "P$1") (pinfunction "1_P$1") (pintype "passive"))
    )
    (net (code "36") (name "Net-(Q6-B)") (class "Default")
      (node (ref "Q6") (pin "2") (pinfunction "B_2") (pintype "passive"))
      (node (ref "R13") (pin "P$1") (pinfunction "1_P$1") (pintype "passive"))
      (node (ref "R14") (pin "P$1") (pinfunction "1_P$1") (pintype "passive"))
    )
    (net (code "37") (name "Net-(Q6-E)") (class "Default")
      (node (ref "Q6") (pin "3") (pinfunction "E_3") (pintype "passive"))
      (node (ref "Q8") (pin "2") (pinfunction "B_2") (pintype "passive"))
      (node (ref "R12") (pin "P$2") (pinfunction "2_P$2") (pintype "passive"))
      (node (ref "R15") (pin "1") (pinfunction "CCW_1") (pintype "passive"))
      (node (ref "R15") (pin "2") (pinfunction "WIPER_2") (pintype "passive"))
    )
    (net (code "38") (name "Net-(Q7-C)") (class "Default")
      (node (ref "Q7") (pin "1") (pinfunction "C_1") (pintype "passive"))
      (node (ref "Q9") (pin "3") (pinfunction "B_3") (pintype "passive"))
      (node (ref "R16") (pin "P$1") (pinfunction "1_P$1") (pintype "passive"))
    )
    (net (code "39") (name "Net-(Q7-E)") (class "Default")
      (node (ref "Q7") (pin "3") (pinfunction "E_3") (pintype "passive"))
      (node (ref "Q9") (pin "2") (pinfunction "C_2") (pintype "passive"))
      (node (ref "R18") (pin "P$2") (pinfunction "2_P$2") (pintype "passive"))
    )
    (net (code "40") (name "Net-(Q10-B)") (class "Default")
      (node (ref "Q10") (pin "3") (pinfunction "B_3") (pintype "passive"))
      (node (ref "Q8") (pin "1") (pinfunction "C_1") (pintype "passive"))
      (node (ref "R17") (pin "P$2") (pinfunction "2_P$2") (pintype "passive"))
    )
    (net (code "41") (name "Net-(Q10-C)") (class "Default")
      (node (ref "Q10") (pin "2") (pinfunction "C_2") (pintype "passive"))
      (node (ref "Q8") (pin "3") (pinfunction "E_3") (pintype "passive"))
      (node (ref "R19") (pin "P$1") (pinfunction "1_P$1") (pintype "passive"))
    )
    (net (code "42") (name "Net-(Q11-C)") (class "Default")
      (node (ref "Q11") (pin "3") (pinfunction "C_3") (pintype "passive"))
      (node (ref "Q12") (pin "1") (pinfunction "C_1") (pintype "passive"))
      (node (ref "Q14") (pin "2") (pinfunction "B_2") (pintype "passive"))
    )
    (net (code "43") (name "Net-(Q11-E)") (class "Default")
      (node (ref "Q11") (pin "1") (pinfunction "E_1") (pintype "passive"))
      (node (ref "R27") (pin "P$2") (pinfunction "2_P$2") (pintype "passive"))
    )
    (net (code "44") (name "Net-(Q12-B)") (class "Default")
      (node (ref "Q12") (pin "2") (pinfunction "B_2") (pintype "passive"))
      (node (ref "Q13") (pin "1") (pinfunction "C_1") (pintype "passive"))
      (node (ref "Q13") (pin "2") (pinfunction "B_2") (pintype "passive"))
      (node (ref "Q14") (pin "3") (pinfunction "E_3") (pintype "passive"))
    )
    (net (code "45") (name "Net-(Q12-E)") (class "Default")
      (node (ref "Q12") (pin "3") (pinfunction "E_3") (pintype "passive"))
      (node (ref "R26") (pin "P$1") (pinfunction "1_P$1") (pintype "passive"))
    )
    (net (code "46") (name "Net-(Q13-E)") (class "Default")
      (node (ref "Q13") (pin "3") (pinfunction "E_3") (pintype "passive"))
      (node (ref "R28") (pin "P$1") (pinfunction "1_P$1") (pintype "passive"))
    )
    (net (code "47") (name "Net-(Q14-C)") (class "Default")
      (node (ref "Q14") (pin "1") (pinfunction "C_1") (pintype "passive"))
      (node (ref "Q15") (pin "2") (pinfunction "B_2") (pintype "passive"))
      (node (ref "V1") (pin "6") (pinfunction "TA_6") (pintype "passive"))
    )
    (net (code "48") (name "Net-(Q15-C)") (class "Default")
      (node (ref "Q15") (pin "1") (pinfunction "C_1") (pintype "passive"))
      (node (ref "Q16") (pin "1") (pinfunction "C_1") (pintype "passive"))
      (node (ref "Q17") (pin "2") (pinfunction "B_2") (pintype "passive"))
      (node (ref "R33") (pin "P$2") (pinfunction "2_P$2") (pintype "passive"))
    )
    (net (code "49") (name "Net-(Q15-E)") (class "Default")
      (node (ref "Q15") (pin "3") (pinfunction "E_3") (pintype "passive"))
      (node (ref "R31") (pin "P$1") (pinfunction "1_P$1") (pintype "passive"))
    )
    (net (code "50") (name "Net-(Q16-B)") (class "Default")
      (node (ref "Q16") (pin "2") (pinfunction "B_2") (pintype "passive"))
      (node (ref "R33") (pin "P$1") (pinfunction "1_P$1") (pintype "passive"))
      (node (ref "R34") (pin "P$1") (pinfunction "1_P$1") (pintype "passive"))
    )
    (net (code "51") (name "Net-(Q16-E)") (class "Default")
      (node (ref "Q16") (pin "3") (pinfunction "E_3") (pintype "passive"))
      (node (ref "Q18") (pin "2") (pinfunction "B_2") (pintype "passive"))
      (node (ref "R32") (pin "P$2") (pinfunction "2_P$2") (pintype "passive"))
      (node (ref "R35") (pin "1") (pinfunction "CCW_1") (pintype "passive"))
      (node (ref "R35") (pin "2") (pinfunction "WIPER_2") (pintype "passive"))
    )
    (net (code "52") (name "Net-(Q17-C)") (class "Default")
      (node (ref "Q17") (pin "1") (pinfunction "C_1") (pintype "passive"))
      (node (ref "Q19") (pin "3") (pinfunction "B_3") (pintype "passive"))
      (node (ref "R36") (pin "P$1") (pinfunction "1_P$1") (pintype "passive"))
    )
    (net (code "53") (name "Net-(Q17-E)") (class "Default")
      (node (ref "Q17") (pin "3") (pinfunction "E_3") (pintype "passive"))
      (node (ref "Q19") (pin "2") (pinfunction "C_2") (pintype "passive"))
      (node (ref "R38") (pin "P$2") (pinfunction "2_P$2") (pintype "passive"))
    )
    (net (code "54") (name "Net-(Q18-C)") (class "Default")
      (node (ref "Q18") (pin "1") (pinfunction "C_1") (pintype "passive"))
      (node (ref "Q20") (pin "3") (pinfunction "B_3") (pintype "passive"))
      (node (ref "R37") (pin "P$2") (pinfunction "2_P$2") (pintype "passive"))
    )
    (net (code "55") (name "Net-(Q18-E)") (class "Default")
      (node (ref "Q18") (pin "3") (pinfunction "E_3") (pintype "passive"))
      (node (ref "Q20") (pin "2") (pinfunction "C_2") (pintype "passive"))
      (node (ref "R39") (pin "P$1") (pinfunction "1_P$1") (pintype "passive"))
    )
    (net (code "56") (name "Net-(Q21-B)") (class "Default")
      (node (ref "Q21") (pin "2") (pinfunction "B_2") (pintype "passive"))
      (node (ref "Q22") (pin "1") (pinfunction "E_1") (pintype "passive"))
      (node (ref "R48") (pin "P$2") (pinfunction "2_P$2") (pintype "passive"))
    )
    (net (code "57") (name "Net-(Q22-B)") (class "Default")
      (node (ref "C22") (pin "1") (pinfunction "1_1") (pintype "passive"))
      (node (ref "C23") (pin "+") (pinfunction "+_+") (pintype "passive"))
      (node (ref "Q22") (pin "2") (pinfunction "B_2") (pintype "passive"))
      (node (ref "R42") (pin "P$2") (pinfunction "2_P$2") (pintype "passive"))
    )
    (net (code "58") (name "Net-(R4-2)") (class "Default")
      (node (ref "C4") (pin "2") (pinfunction "2_2") (pintype "passive"))
      (node (ref "R4") (pin "P$2") (pinfunction "2_P$2") (pintype "passive"))
      (node (ref "R5") (pin "P$2") (pinfunction "2_P$2") (pintype "passive"))
    )
    (net (code "59") (name "Net-(R5-1)") (class "Default")
      (node (ref "R5") (pin "P$1") (pinfunction "1_P$1") (pintype "passive"))
      (node (ref "V1") (pin "2") (pinfunction "TG_2") (pintype "passive"))
    )
    (net (code "60") (name "Net-(R10-2)") (class "Default")
      (node (ref "R10") (pin "P$2") (pinfunction "2_P$2") (pintype "passive"))
      (node (ref "R9") (pin "P$2") (pinfunction "2_P$2") (pintype "passive"))
      (node (ref "V1") (pin "3") (pinfunction "TK_3") (pintype "passive"))
    )
    (net (code "61") (name "Net-(R14-2)") (class "Default")
      (node (ref "R14") (pin "P$2") (pinfunction "2_P$2") (pintype "passive"))
      (node (ref "R15") (pin "3") (pinfunction "CW_3") (pintype "passive"))
    )
    (net (code "62") (name "Net-(R24-2)") (class "Default")
      (node (ref "C13") (pin "2") (pinfunction "2_2") (pintype "passive"))
      (node (ref "R24") (pin "P$2") (pinfunction "2_P$2") (pintype "passive"))
      (node (ref "R25") (pin "P$2") (pinfunction "2_P$2") (pintype "passive"))
    )
    (net (code "63") (name "Net-(R25-1)") (class "Default")
      (node (ref "R25") (pin "P$1") (pinfunction "1_P$1") (pintype "passive"))
      (node (ref "V1") (pin "7") (pinfunction "TG_7") (pintype "passive"))
    )
    (net (code "64") (name "Net-(R29-2)") (class "Default")
      (node (ref "R29") (pin "P$2") (pinfunction "2_P$2") (pintype "passive"))
      (node (ref "R30") (pin "P$2") (pinfunction "2_P$2") (pintype "passive"))
      (node (ref "V1") (pin "8") (pinfunction "TK_8") (pintype "passive"))
    )
    (net (code "65") (name "Net-(R34-2)") (class "Default")
      (node (ref "R34") (pin "P$2") (pinfunction "2_P$2") (pintype "passive"))
      (node (ref "R35") (pin "3") (pinfunction "CW_3") (pintype "passive"))
    )
    (net (code "66") (name "Net-(R47-2)") (class "Default")
      (node (ref "D7") (pin "A") (pinfunction "A_A") (pintype "passive"))
      (node (ref "R47") (pin "P$2") (pinfunction "2_P$2") (pintype "passive"))
    )
    (net (code "67") (name "OUT_L") (class "Default")
      (node (ref "C8") (pin "-") (pinfunction "-_-") (pintype "passive"))
      (node (ref "C9") (pin "-") (pinfunction "-_-") (pintype "passive"))
      (node (ref "J2") (pin "T") (pinfunction "LEFT_T") (pintype "bidirectional"))
      (node (ref "R20") (pin "P$2") (pinfunction "2_P$2") (pintype "passive"))
    )
    (net (code "68") (name "OUT_R") (class "Default")
      (node (ref "C17") (pin "-") (pinfunction "-_-") (pintype "passive"))
      (node (ref "C18") (pin "-") (pinfunction "-_-") (pintype "passive"))
      (node (ref "J2") (pin "R") (pinfunction "RIGHT_R") (pintype "bidirectional"))
      (node (ref "R40") (pin "P$2") (pinfunction "2_P$2") (pintype "passive"))
    )
    (net (code "69") (name "VCC") (class "Default")
      (node (ref "C12") (pin "2") (pinfunction "2_2") (pintype "passive"))
      (node (ref "C16") (pin "+") (pinfunction "+_+") (pintype "passive"))
      (node (ref "C2") (pin "2") (pinfunction "2_2") (pintype "passive"))
      (node (ref "C28") (pin "1") (pinfunction "+_1") (pintype "passive"))
      (node (ref "C7") (pin "+") (pinfunction "+_+") (pintype "passive"))
      (node (ref "D4") (pin "A") (pinfunction "A_A") (pintype "passive"))
      (node (ref "D5") (pin "C") (pinfunction "C_C") (pintype "passive"))
      (node (ref "IC1") (pin "7") (pinfunction "V+_7") (pintype "power_in"))
      (node (ref "IC2") (pin "7") (pinfunction "V+_7") (pintype "power_in"))
      (node (ref "IC3") (pin "2") (pinfunction "OUT_2") (pintype "passive"))
      (node (ref "Q19") (pin "1") (pinfunction "E_1") (pintype "passive"))
      (node (ref "Q9") (pin "1") (pinfunction "E_1") (pintype "passive"))
      (node (ref "R16") (pin "P$2") (pinfunction "2_P$2") (pintype "passive"))
      (node (ref "R2") (pin "P$2") (pinfunction "2_P$2") (pintype "passive"))
      (node (ref "R22") (pin "P$2") (pinfunction "2_P$2") (pintype "passive"))
      (node (ref "R36") (pin "P$2") (pinfunction "2_P$2") (pintype "passive"))
      (node (ref "R43") (pin "P$1") (pinfunction "1_P$1") (pintype "passive"))
      (node (ref "R47") (pin "P$1") (pinfunction "1_P$1") (pintype "passive"))
    )
    (net (code "70") (name "unconnected-(IC1-ON1-Pad1)") (class "Default")
      (node (ref "IC1") (pin "1") (pinfunction "ON1_1") (pintype "passive"))
    )
    (net (code "71") (name "unconnected-(IC1-ON2-Pad5)") (class "Default")
      (node (ref "IC1") (pin "5") (pinfunction "ON2_5") (pintype "passive"))
    )
    (net (code "72") (name "unconnected-(IC1-OPT-Pad8)") (class "Default")
      (node (ref "IC1") (pin "8") (pinfunction "OPT_8") (pintype "passive"))
    )
    (net (code "73") (name "unconnected-(IC2-ON1-Pad1)") (class "Default")
      (node (ref "IC2") (pin "1") (pinfunction "ON1_1") (pintype "passive"))
    )
    (net (code "74") (name "unconnected-(IC2-ON2-Pad5)") (class "Default")
      (node (ref "IC2") (pin "5") (pinfunction "ON2_5") (pintype "passive"))
    )
    (net (code "75") (name "unconnected-(IC2-OPT-Pad8)") (class "Default")
      (node (ref "IC2") (pin "8") (pinfunction "OPT_8") (pintype "passive"))
    )
    (net (code "76") (name "unconnected-(V1A-H2-Pad9)") (class "Default")
      (node (ref "V1") (pin "9") (pinfunction "H2_9") (pintype "passive"))
    )
  )
)
